# Enclosure_85x58_BHC.net
KiCad netlist of a schematic drawn in EAGLE
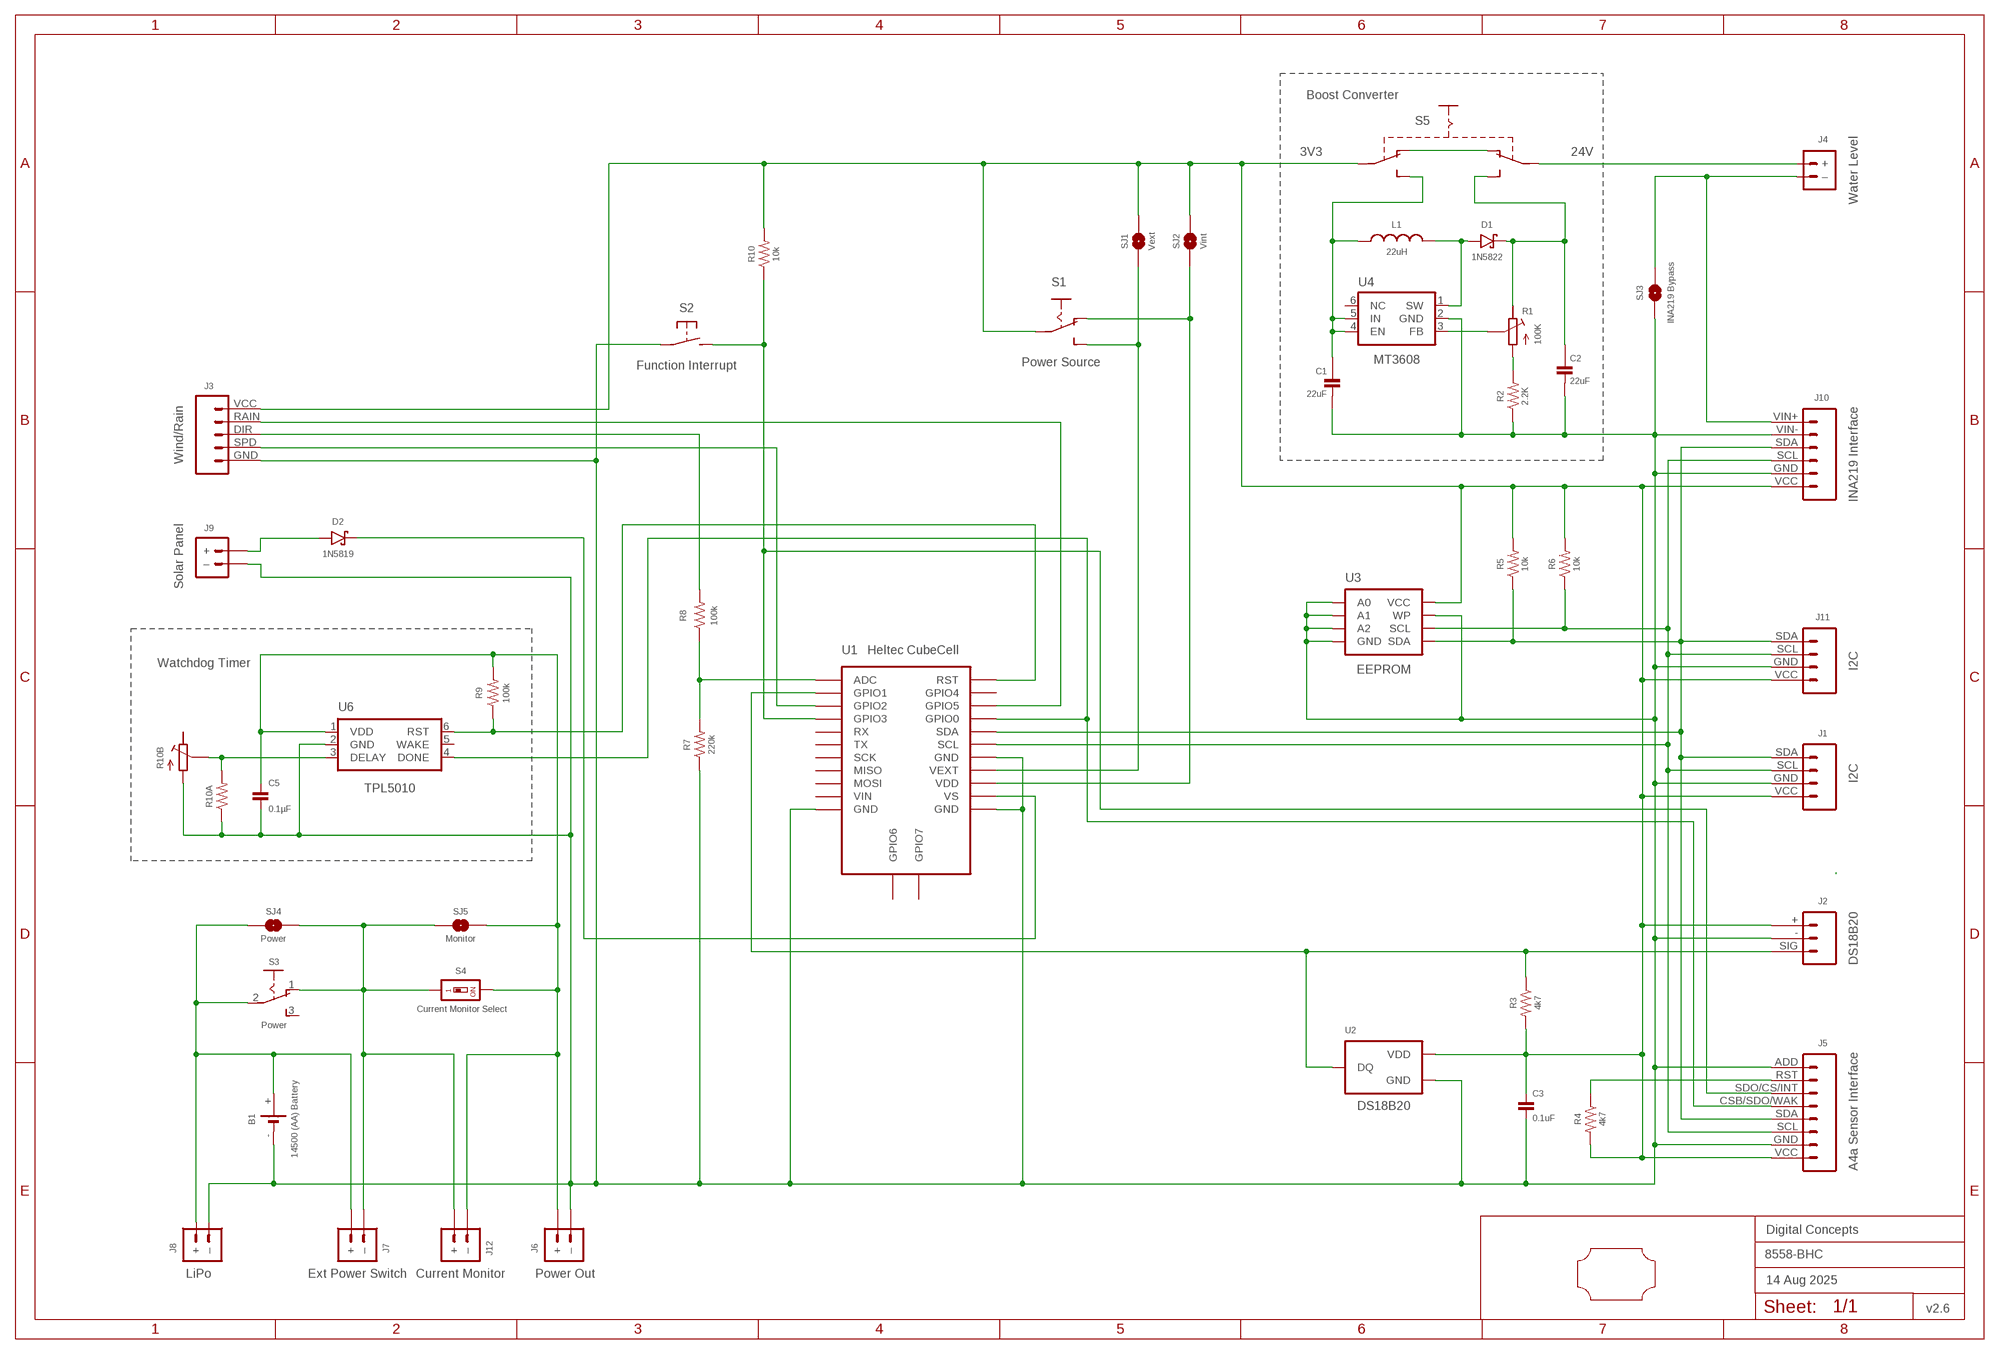
[diagram p0: schematic, sheet 1]

(export (version "E")
  (design (tool "Eeschema 10.0.6"))
  (components
    (comp (ref "B1")
      (value "14500 (AA) Battery")
      (footprint "eagle-import:BATTERY-14500")
      (libsource (lib "eagle-import") (part "BATTERY-HOLDER-14500(AA)"))
    )
    (comp (ref "C1")
      (value "22uF")
      (footprint "eagle-import:C1206")
      (libsource (lib "eagle-import") (part "CAPACITOR-1206"))
    )
    (comp (ref "C2")
      (value "22uF")
      (footprint "eagle-import:C1206")
      (libsource (lib "eagle-import") (part "CAPACITOR-1206"))
    )
    (comp (ref "C3")
      (value "0.1uF")
      (footprint "eagle-import:C0805")
      (libsource (lib "eagle-import") (part "CAPACITOR-0805"))
    )
    (comp (ref "C5")
      (value "0.1µF")
      (footprint "eagle-import:C0805")
      (libsource (lib "eagle-import") (part "CAPACITOR-0805"))
    )
    (comp (ref "D1")
      (value "1N5822")
      (footprint "eagle-import:DIODE_SMB")
      (libsource (lib "eagle-import") (part "DIODE-SCHOTTKY-1N5822"))
    )
    (comp (ref "D2")
      (value "1N5819")
      (footprint "eagle-import:SOD-123")
      (libsource (lib "eagle-import") (part "1N5819-SOD-123"))
    )
    (comp (ref "J1")
      (value "I2C")
      (footprint "eagle-import:JST-PH2.0-4-VERTICAL-I2C")
      (libsource (lib "eagle-import") (part "JST-PH2.0-4-VERTICAL-I2C"))
    )
    (comp (ref "J2")
      (value "DS18B20")
      (footprint "eagle-import:JST-PH2.0-3-VERTICAL")
      (libsource (lib "eagle-import") (part "JST-PH2.0-3-VERTICAL-DS18B20"))
    )
    (comp (ref "J3")
      (value "Wind/Rain")
      (footprint "eagle-import:JST-PH2.0-5-WEATHER")
      (libsource (lib "eagle-import") (part "JST-PH2.0-5-VERTICAL-WEATHER"))
    )
    (comp (ref "J4")
      (value "Water Level")
      (footprint "eagle-import:JST-PH2.0-2-VERTICAL=POWER")
      (libsource (lib "eagle-import") (part "JST-PH2.0-2-VERTICAL"))
    )
    (comp (ref "J5")
      (value "A4a Sensor Interface")
      (footprint "eagle-import:CONN_08-SENSOR")
      (libsource (lib "eagle-import") (part "HEADER-1X8-SENSOR"))
    )
    (comp (ref "J6")
      (value "Power Out")
      (footprint "eagle-import:JST-GH1.25-2-HORIZONTAL")
      (libsource (lib "eagle-import") (part "JST-GH1.25-2-HORIZONTAL-POWER"))
    )
    (comp (ref "J7")
      (value "Ext Power Switch")
      (footprint "eagle-import:JST-PH2.0-2-DUAL-POWER")
      (libsource (lib "eagle-import") (part "JST-PH2.0-2-DUAL-POWERJST-PTH-2"))
    )
    (comp (ref "J8")
      (value "LiPo")
      (footprint "eagle-import:JST-PH2.0-2-HORIZONTAL")
      (libsource (lib "eagle-import") (part "JST-PH2.0-2-MALE-HORIZONTALJST-PTH-2"))
    )
    (comp (ref "J9")
      (value "Solar Panel")
      (footprint "eagle-import:JST-PH2.0-2-DUAL-POWER")
      (libsource (lib "eagle-import") (part "JST-PH2.0-2-DUAL-POWERJST-PTH-2"))
    )
    (comp (ref "J10")
      (value "INA219 Interface")
      (footprint "eagle-import:CONN_06-INA219")
      (libsource (lib "eagle-import") (part "INA219-I2C-MODULE"))
    )
    (comp (ref "J11")
      (value "I2C")
      (footprint "eagle-import:JST-PH2.0-4-HORIZONTAL-I2C")
      (libsource (lib "eagle-import") (part "JST-PH2.0-4-HORIZONTAL-I2C"))
    )
    (comp (ref "J12")
      (value "Current Monitor")
      (footprint "eagle-import:JST-PH2.0-2-HORIZONTAL-POWER")
      (libsource (lib "eagle-import") (part "JST-PH2.0-2-HORIZONTAL-POWERJST-PTH-2"))
    )
    (comp (ref "L1")
      (value "22uH")
      (footprint "eagle-import:CDRH104R+6D28")
      (libsource (lib "eagle-import") (part "INDUCTOR-CDRH104R/6D28L5038P"))
    )
    (comp (ref "R1")
      (value "100K")
      (footprint "eagle-import:RTRIM64P")
      (libsource (lib "eagle-import") (part "RESISTOR-TRIMM-BAOTER-HORIZONTAL"))
    )
    (comp (ref "R2")
      (value "2.2K")
      (footprint "eagle-import:R0805")
      (libsource (lib "eagle-import") (part "RESISTORR0805"))
    )
    (comp (ref "R3")
      (value "4k7")
      (footprint "eagle-import:R0805")
      (libsource (lib "eagle-import") (part "RESISTORR0805"))
    )
    (comp (ref "R4")
      (value "4k7")
      (footprint "eagle-import:R0805")
      (libsource (lib "eagle-import") (part "RESISTORR0805"))
    )
    (comp (ref "R5")
      (value "10k")
      (footprint "eagle-import:R0805")
      (libsource (lib "eagle-import") (part "RESISTORR0805"))
    )
    (comp (ref "R6")
      (value "10k")
      (footprint "eagle-import:R0805")
      (libsource (lib "eagle-import") (part "RESISTORR0805"))
    )
    (comp (ref "R7")
      (value "220k")
      (footprint "eagle-import:R0805")
      (libsource (lib "eagle-import") (part "RESISTORR0805"))
    )
    (comp (ref "R8")
      (value "100k")
      (footprint "eagle-import:R0805")
      (libsource (lib "eagle-import") (part "RESISTORR0805"))
    )
    (comp (ref "R9")
      (value "100k")
      (footprint "eagle-import:R0805")
      (libsource (lib "eagle-import") (part "RESISTORR0805"))
    )
    (comp (ref "R10")
      (value "10k")
      (footprint "eagle-import:R0805")
      (libsource (lib "eagle-import") (part "RESISTORR0805"))
    )
    (comp (ref "R10A")
      (value "RESISTORR0805")
      (footprint "eagle-import:R0805")
      (libsource (lib "eagle-import") (part "RESISTORR0805"))
    )
    (comp (ref "R10B")
      (value "RESISTOR-TRIMM-33")
      (footprint "eagle-import:RTRIM3_3")
      (libsource (lib "eagle-import") (part "RESISTOR-TRIMM-33"))
    )
    (comp (ref "S1")
      (value "Power Source")
      (footprint "eagle-import:SWITCH-SPDT-SMT")
      (libsource (lib "eagle-import") (part "SWITCH-SLIDE-SPDT-SMT"))
    )
    (comp (ref "S2")
      (value "Function Interrupt")
      (footprint "eagle-import:SWITCH-2-PAD")
      (libsource (lib "eagle-import") (part "SWITCH-MOMENTARY-2-PIN"))
    )
    (comp (ref "S3")
      (value "Power")
      (footprint "eagle-import:SWITCH-SLIDE-SPDT")
      (libsource (lib "eagle-import") (part "SWITCH-SLIDE-SPDT"))
    )
    (comp (ref "S4")
      (value "Current Monitor Select")
      (footprint "eagle-import:SMD-001")
      (libsource (lib "eagle-import") (part "SWITCH-DIP-SWS001"))
    )
    (comp (ref "S5")
      (value "SWITCH-SLIDE-DPDT-PTH-S")
      (footprint "eagle-import:SWITCH-DPDT-PTH")
      (libsource (lib "eagle-import") (part "SWITCH-SLIDE-DPDT-PTH-S"))
    )
    (comp (ref "SJ1")
      (value "Vext")
      (footprint "eagle-import:SJ")
      (libsource (lib "eagle-import") (part "SJ"))
    )
    (comp (ref "SJ2")
      (value "Vint")
      (footprint "eagle-import:SJ-VIA-1")
      (libsource (lib "eagle-import") (part "SJ-V-1"))
    )
    (comp (ref "SJ3")
      (value "INA219 Bypass")
      (footprint "eagle-import:SJ")
      (libsource (lib "eagle-import") (part "SJ"))
    )
    (comp (ref "SJ4")
      (value "Power")
      (footprint "eagle-import:SJ")
      (libsource (lib "eagle-import") (part "SJ"))
    )
    (comp (ref "SJ5")
      (value "Monitor")
      (footprint "eagle-import:SJ")
      (libsource (lib "eagle-import") (part "SJ"))
    )
    (comp (ref "U$1")
      (value "PCB-OUTLINE-C-85X58")
      (footprint "eagle-import:PROTO-28X18-OUTLINE-C")
      (libsource (lib "eagle-import") (part "PCB-OUTLINE-C-85X58"))
    )
    (comp (ref "U1")
      (value "Heltec CubeCell")
      (footprint "eagle-import:HELTEC-CUBECELL")
      (libsource (lib "eagle-import") (part "HELTEC-CUBECELL"))
    )
    (comp (ref "U2")
      (value "DS18B20")
      (footprint "eagle-import:TO-92")
      (fields (field (name "MF") "Maxim Integrated"))
      (libsource (lib "eagle-import") (part "THERMOMETER-DS18B20"))
    )
    (comp (ref "U3")
      (value "EEPROM")
      (footprint "eagle-import:SOP-8")
      (libsource (lib "eagle-import") (part "AT24CXX-EEPROM"))
    )
    (comp (ref "U4")
      (value "MT3608")
      (footprint "eagle-import:SOT-23-6@1")
      (libsource (lib "eagle-import") (part "MT3608"))
    )
    (comp (ref "U6")
      (value "TPL5010")
      (footprint "eagle-import:SOT-23-6")
      (libsource (lib "eagle-import") (part "TPL5010DDCR"))
    )
  )
  (nets
    (net (code "1") (name "Net-(D2-PadA)") (class "Default")
      (node (ref "D2") (pin "A") (pinfunction "A_A") (pintype "passive"))
      (node (ref "J9") (pin "+") (pinfunction "+_+") (pintype "power_in"))
    )
    (net (code "2") (name "Net-(D2-PadC)") (class "Default")
      (node (ref "D2") (pin "C") (pinfunction "C_C") (pintype "passive"))
      (node (ref "U1") (pin "VS") (pinfunction "VS_VS") (pintype "bidirectional"))
    )
    (net (code "3") (name "Net-(J1-1)") (class "Default")
      (node (ref "J1") (pin "SDA") (pinfunction "1_SDA") (pintype "passive"))
      (node (ref "J10") (pin "SDA") (pinfunction "4_SDA") (pintype "passive"))
      (node (ref "J11") (pin "SDA") (pinfunction "1_SDA") (pintype "passive"))
      (node (ref "J5") (pin "SDA") (pinfunction "4_SDA") (pintype "passive"))
      (node (ref "R5") (pin "1") (pinfunction "1_1") (pintype "passive"))
      (node (ref "U1") (pin "SDA") (pinfunction "SDA_SDA") (pintype "bidirectional"))
      (node (ref "U3") (pin "P$5") (pinfunction "SDA_P$5") (pintype "bidirectional"))
    )
    (net (code "4") (name "Net-(J1-2)") (class "Default")
      (node (ref "J1") (pin "SCL") (pinfunction "2_SCL") (pintype "passive"))
      (node (ref "J10") (pin "SCL") (pinfunction "3_SCL") (pintype "passive"))
      (node (ref "J11") (pin "SCL") (pinfunction "2_SCL") (pintype "passive"))
      (node (ref "J5") (pin "SCL") (pinfunction "3_SCL") (pintype "passive"))
      (node (ref "R6") (pin "1") (pinfunction "1_1") (pintype "passive"))
      (node (ref "U1") (pin "SCL") (pinfunction "SCL_SCL") (pintype "bidirectional"))
      (node (ref "U3") (pin "P$6") (pinfunction "SCL_P$6") (pintype "bidirectional"))
    )
    (net (code "5") (name "Net-(J1-3)") (class "Default")
      (node (ref "B1") (pin "-") (pinfunction "-_-") (pintype "power_in"))
      (node (ref "C1") (pin "2") (pinfunction "2_2") (pintype "passive"))
      (node (ref "C2") (pin "2") (pinfunction "2_2") (pintype "passive"))
      (node (ref "C3") (pin "2") (pinfunction "2_2") (pintype "passive"))
      (node (ref "C5") (pin "2") (pinfunction "2_2") (pintype "passive"))
      (node (ref "J1") (pin "GND") (pinfunction "3_GND") (pintype "passive"))
      (node (ref "J10") (pin "GND") (pinfunction "2_GND") (pintype "passive"))
      (node (ref "J10") (pin "VIN-") (pinfunction "5_VIN-") (pintype "passive"))
      (node (ref "J11") (pin "GND") (pinfunction "3_GND") (pintype "passive"))
      (node (ref "J2") (pin "-") (pinfunction "2_-") (pintype "passive"))
      (node (ref "J3") (pin "GND") (pinfunction "5_GND") (pintype "passive"))
      (node (ref "J5") (pin "ADD") (pinfunction "8_ADD") (pintype "passive"))
      (node (ref "J5") (pin "GND") (pinfunction "2_GND") (pintype "passive"))
      (node (ref "J6") (pin "-") (pinfunction "–_-") (pintype "power_in"))
      (node (ref "J8") (pin "-") (pinfunction "–_-") (pintype "power_in"))
      (node (ref "J9") (pin "-") (pinfunction "–_-") (pintype "power_in"))
      (node (ref "R10A") (pin "1") (pinfunction "1_1") (pintype "passive"))
      (node (ref "R10B") (pin "1") (pinfunction "A_1") (pintype "passive"))
      (node (ref "R2") (pin "1") (pinfunction "1_1") (pintype "passive"))
      (node (ref "R7") (pin "1") (pinfunction "1_1") (pintype "passive"))
      (node (ref "S2") (pin "P$1") (pinfunction "P_P$1") (pintype "passive"))
      (node (ref "SJ3") (pin "1") (pinfunction "1_1") (pintype "passive"))
      (node (ref "U1") (pin "GND@11") (pinfunction "GND_GND@11") (pintype "bidirectional"))
      (node (ref "U1") (pin "GND@14") (pinfunction "GND_GND@14") (pintype "bidirectional"))
      (node (ref "U1") (pin "GND@18") (pinfunction "GND_GND@18") (pintype "bidirectional"))
      (node (ref "U2") (pin "1") (pinfunction "GND_1") (pintype "power_in"))
      (node (ref "U3") (pin "P$1") (pinfunction "A0_P$1") (pintype "bidirectional"))
      (node (ref "U3") (pin "P$2") (pinfunction "A1_P$2") (pintype "bidirectional"))
      (node (ref "U3") (pin "P$3") (pinfunction "A2_P$3") (pintype "bidirectional"))
      (node (ref "U3") (pin "P$4") (pinfunction "GND_P$4") (pintype "bidirectional"))
      (node (ref "U3") (pin "P$7") (pinfunction "WP_P$7") (pintype "bidirectional"))
      (node (ref "U4") (pin "2") (pinfunction "GND_2") (pintype "power_in"))
      (node (ref "U6") (pin "2") (pinfunction "GND_2") (pintype "power_in"))
    )
    (net (code "6") (name "Net-(J1-4)") (class "Default")
      (node (ref "C3") (pin "1") (pinfunction "1_1") (pintype "passive"))
      (node (ref "J1") (pin "VCC") (pinfunction "4_VCC") (pintype "passive"))
      (node (ref "J10") (pin "VCC") (pinfunction "1_VCC") (pintype "passive"))
      (node (ref "J11") (pin "VCC") (pinfunction "4_VCC") (pintype "passive"))
      (node (ref "J2") (pin "+") (pinfunction "3_+") (pintype "passive"))
      (node (ref "J3") (pin "VCC") (pinfunction "1_VCC") (pintype "passive"))
      (node (ref "J5") (pin "VCC") (pinfunction "1_VCC") (pintype "passive"))
      (node (ref "R10") (pin "2") (pinfunction "2_2") (pintype "passive"))
      (node (ref "R3") (pin "2") (pinfunction "2_2") (pintype "passive"))
      (node (ref "R4") (pin "2") (pinfunction "2_2") (pintype "passive"))
      (node (ref "R5") (pin "2") (pinfunction "2_2") (pintype "passive"))
      (node (ref "R6") (pin "2") (pinfunction "2_2") (pintype "passive"))
      (node (ref "S1") (pin "COMMON") (pinfunction "P_COMMON") (pintype "passive"))
      (node (ref "S5") (pin "P$5") (pinfunction "P2_P$5") (pintype "passive"))
      (node (ref "SJ1") (pin "1") (pinfunction "1_1") (pintype "passive"))
      (node (ref "SJ2") (pin "1") (pinfunction "1_1") (pintype "passive"))
      (node (ref "SJ2") (pin "1@V") (pinfunction "1_1@V") (pintype "passive"))
      (node (ref "U2") (pin "3") (pinfunction "VDD_3") (pintype "power_in"))
      (node (ref "U3") (pin "P$8") (pinfunction "VCC_P$8") (pintype "bidirectional"))
    )
    (net (code "7") (name "Net-(J2-1)") (class "Default")
      (node (ref "J2") (pin "SIG") (pinfunction "1_SIG") (pintype "passive"))
      (node (ref "R3") (pin "1") (pinfunction "1_1") (pintype "passive"))
      (node (ref "U1") (pin "GPIO1") (pinfunction "GPIO1_GPIO1") (pintype "bidirectional"))
      (node (ref "U2") (pin "2") (pinfunction "DQ_2") (pintype "bidirectional"))
    )
    (net (code "8") (name "Net-(J3-2)") (class "Default")
      (node (ref "J3") (pin "RAIN") (pinfunction "2_RAIN") (pintype "passive"))
      (node (ref "U1") (pin "GPIO5") (pinfunction "GPIO5_GPIO5") (pintype "bidirectional"))
    )
    (net (code "9") (name "Net-(J3-3)") (class "Default")
      (node (ref "J3") (pin "DIR") (pinfunction "3_DIR") (pintype "passive"))
      (node (ref "R8") (pin "2") (pinfunction "2_2") (pintype "passive"))
    )
    (net (code "10") (name "Net-(J3-4)") (class "Default")
      (node (ref "J3") (pin "SPD") (pinfunction "4_SPD") (pintype "passive"))
      (node (ref "U1") (pin "GPIO2") (pinfunction "GPIO2_GPIO2") (pintype "bidirectional"))
    )
    (net (code "11") (name "Net-(J5-5)") (class "Default")
      (node (ref "J5") (pin "CSB/SDO/WAK") (pinfunction "5_CSB/SDO/WAK") (pintype "passive"))
      (node (ref "U1") (pin "GPIO0") (pinfunction "GPIO0_GPIO0") (pintype "bidirectional"))
      (node (ref "U6") (pin "4") (pinfunction "DONE_4") (pintype "input"))
    )
    (net (code "12") (name "Net-(J5-6)") (class "Default")
      (node (ref "J5") (pin "SDO/CS/INT") (pinfunction "6_SDO/CS/INT") (pintype "passive"))
      (node (ref "R10") (pin "1") (pinfunction "1_1") (pintype "passive"))
      (node (ref "S2") (pin "P$2") (pinfunction "S_P$2") (pintype "passive"))
      (node (ref "U1") (pin "GPIO3") (pinfunction "GPIO3_GPIO3") (pintype "bidirectional"))
    )
    (net (code "13") (name "Net-(J5-7)") (class "Default")
      (node (ref "J5") (pin "RST") (pinfunction "7_RST") (pintype "passive"))
      (node (ref "R4") (pin "1") (pinfunction "1_1") (pintype "passive"))
    )
    (net (code "14") (name "Net-(J7-–)") (class "Default")
      (node (ref "J12") (pin "+") (pinfunction "+_+") (pintype "power_in"))
      (node (ref "J7") (pin "-") (pinfunction "–_-") (pintype "power_in"))
      (node (ref "S3") (pin "1") (pinfunction "O_1") (pintype "passive"))
      (node (ref "S4") (pin "1") (pinfunction "1_1") (pintype "passive"))
      (node (ref "SJ4") (pin "1") (pinfunction "1_1") (pintype "passive"))
      (node (ref "SJ5") (pin "2") (pinfunction "2_2") (pintype "passive"))
    )
    (net (code "15") (name "Net-(J10-6)") (class "Default")
      (node (ref "J10") (pin "VIN+") (pinfunction "6_VIN+") (pintype "passive"))
      (node (ref "J4") (pin "-") (pinfunction "–_-") (pintype "power_in"))
      (node (ref "SJ3") (pin "2") (pinfunction "2_2") (pintype "passive"))
    )
    (net (code "16") (name "Net-(J12-–)") (class "Default")
      (node (ref "C5") (pin "1") (pinfunction "1_1") (pintype "passive"))
      (node (ref "J12") (pin "-") (pinfunction "–_-") (pintype "power_in"))
      (node (ref "J6") (pin "+") (pinfunction "+_+") (pintype "power_in"))
      (node (ref "R9") (pin "2") (pinfunction "2_2") (pintype "passive"))
      (node (ref "S4") (pin "2") (pinfunction "2_2") (pintype "passive"))
      (node (ref "SJ5") (pin "1") (pinfunction "1_1") (pintype "passive"))
      (node (ref "U6") (pin "1") (pinfunction "VDD_1") (pintype "power_in"))
    )
    (net (code "17") (name "Net-(R1-A)") (class "Default")
      (node (ref "R1") (pin "1") (pinfunction "A_1") (pintype "passive"))
      (node (ref "R2") (pin "2") (pinfunction "2_2") (pintype "passive"))
    )
    (net (code "18") (name "Net-(R1-E)") (class "Default")
      (node (ref "C2") (pin "1") (pinfunction "1_1") (pintype "passive"))
      (node (ref "D1") (pin "C") (pinfunction "C_C") (pintype "passive"))
      (node (ref "R1") (pin "3") (pinfunction "E_3") (pintype "passive"))
      (node (ref "S5") (pin "P$3") (pinfunction "S1_P$3") (pintype "passive"))
    )
    (net (code "19") (name "Net-(R1-S)") (class "Default")
      (node (ref "R1") (pin "2") (pinfunction "S_2") (pintype "passive"))
      (node (ref "U4") (pin "3") (pinfunction "FB_3") (pintype "input"))
    )
    (net (code "20") (name "Net-(R7-Pad2)") (class "Default")
      (node (ref "R7") (pin "2") (pinfunction "2_2") (pintype "passive"))
      (node (ref "R8") (pin "1") (pinfunction "1_1") (pintype "passive"))
      (node (ref "U1") (pin "ADC") (pinfunction "ADC_ADC") (pintype "bidirectional"))
    )
    (net (code "21") (name "Net-(R10B-S)") (class "Default")
      (node (ref "R10A") (pin "2") (pinfunction "2_2") (pintype "passive"))
      (node (ref "R10B") (pin "2") (pinfunction "S_2") (pintype "passive"))
      (node (ref "U6") (pin "3") (pinfunction "DELAY_3") (pintype "input"))
    )
    (net (code "22") (name "Net-(S1-O)") (class "Default")
      (node (ref "S1") (pin "P$1") (pinfunction "O_P$1") (pintype "passive"))
      (node (ref "SJ2") (pin "2") (pinfunction "2_2") (pintype "passive"))
      (node (ref "U1") (pin "VDD") (pinfunction "VDD_VDD") (pintype "bidirectional"))
    )
    (net (code "23") (name "Net-(S1-S)") (class "Default")
      (node (ref "S1") (pin "P$2") (pinfunction "S_P$2") (pintype "passive"))
      (node (ref "SJ1") (pin "2") (pinfunction "2_2") (pintype "passive"))
      (node (ref "U1") (pin "VEXT") (pinfunction "VEXT_VEXT") (pintype "bidirectional"))
    )
    (net (code "24") (name "Net-(S3-P)") (class "Default")
      (node (ref "B1") (pin "+") (pinfunction "+_+") (pintype "power_in"))
      (node (ref "J7") (pin "+") (pinfunction "+_+") (pintype "power_in"))
      (node (ref "J8") (pin "+") (pinfunction "+_+") (pintype "power_in"))
      (node (ref "S3") (pin "2") (pinfunction "P_2") (pintype "passive"))
      (node (ref "SJ4") (pin "2") (pinfunction "2_2") (pintype "passive"))
    )
    (net (code "25") (name "Net-(S5-O1)") (class "Default")
      (node (ref "S5") (pin "P$1") (pinfunction "O1_P$1") (pintype "passive"))
      (node (ref "S5") (pin "P$4") (pinfunction "O2_P$4") (pintype "passive"))
    )
    (net (code "26") (name "Net-(S5-P1)") (class "Default")
      (node (ref "J4") (pin "+") (pinfunction "+_+") (pintype "power_in"))
      (node (ref "S5") (pin "P$2") (pinfunction "P1_P$2") (pintype "passive"))
    )
    (net (code "27") (name "Net-(S5-S2)") (class "Default")
      (node (ref "C1") (pin "1") (pinfunction "1_1") (pintype "passive"))
      (node (ref "L1") (pin "2") (pinfunction "2_2") (pintype "passive"))
      (node (ref "S5") (pin "P$6") (pinfunction "S2_P$6") (pintype "passive"))
      (node (ref "U4") (pin "4") (pinfunction "EN_4") (pintype "input"))
      (node (ref "U4") (pin "5") (pinfunction "IN_5") (pintype "power_in"))
    )
    (net (code "28") (name "Net-(U4-SW)") (class "Default")
      (node (ref "D1") (pin "A") (pinfunction "A_A") (pintype "passive"))
      (node (ref "L1") (pin "1") (pinfunction "1_1") (pintype "passive"))
      (node (ref "U4") (pin "1") (pinfunction "SW_1") (pintype "power_in"))
    )
    (net (code "29") (name "Net-(U6-RST)") (class "Default")
      (node (ref "R9") (pin "1") (pinfunction "1_1") (pintype "passive"))
      (node (ref "U1") (pin "RST") (pinfunction "RST_RST") (pintype "bidirectional"))
      (node (ref "U6") (pin "6") (pinfunction "RST_6") (pintype "output"))
    )
    (net (code "30") (name "unconnected-(R10B-E-Pad3)") (class "Default")
      (node (ref "R10B") (pin "3") (pinfunction "E_3") (pintype "passive"))
    )
    (net (code "31") (name "unconnected-(S3-S-Pad3)") (class "Default")
      (node (ref "S3") (pin "3") (pinfunction "S_3") (pintype "passive"))
    )
    (net (code "32") (name "unconnected-(U1-PadGPIO4)") (class "Default")
      (node (ref "U1") (pin "GPIO4") (pinfunction "GPIO4_GPIO4") (pintype "bidirectional"))
    )
    (net (code "33") (name "unconnected-(U1-PadGPIO6)") (class "Default")
      (node (ref "U1") (pin "GPIO6") (pinfunction "GPIO6_GPIO6") (pintype "bidirectional"))
    )
    (net (code "34") (name "unconnected-(U1-PadGPIO7)") (class "Default")
      (node (ref "U1") (pin "GPIO7") (pinfunction "GPIO7_GPIO7") (pintype "bidirectional"))
    )
    (net (code "35") (name "unconnected-(U1-PadMISO)") (class "Default")
      (node (ref "U1") (pin "MISO") (pinfunction "MISO_MISO") (pintype "bidirectional"))
    )
    (net (code "36") (name "unconnected-(U1-PadMOSI)") (class "Default")
      (node (ref "U1") (pin "MOSI") (pinfunction "MOSI_MOSI") (pintype "bidirectional"))
    )
    (net (code "37") (name "unconnected-(U1-PadRX)") (class "Default")
      (node (ref "U1") (pin "RX") (pinfunction "RX_RX") (pintype "bidirectional"))
    )
    (net (code "38") (name "unconnected-(U1-PadSCK)") (class "Default")
      (node (ref "U1") (pin "SCK") (pinfunction "SCK_SCK") (pintype "bidirectional"))
    )
    (net (code "39") (name "unconnected-(U1-PadTX)") (class "Default")
      (node (ref "U1") (pin "TX") (pinfunction "TX_TX") (pintype "bidirectional"))
    )
    (net (code "40") (name "unconnected-(U1-PadVIN)") (class "Default")
      (node (ref "U1") (pin "VIN") (pinfunction "VIN_VIN") (pintype "bidirectional"))
    )
    (net (code "41") (name "unconnected-(U4-NC-Pad6)") (class "Default")
      (node (ref "U4") (pin "6") (pinfunction "NC_6") (pintype "no_connect"))
    )
    (net (code "42") (name "unconnected-(U6-WAKE-Pad5)") (class "Default")
      (node (ref "U6") (pin "5") (pinfunction "WAKE_5") (pintype "output"))
    )
  )
)
